# Display.net
KiCad netlist of a schematic drawn in Altium Designer
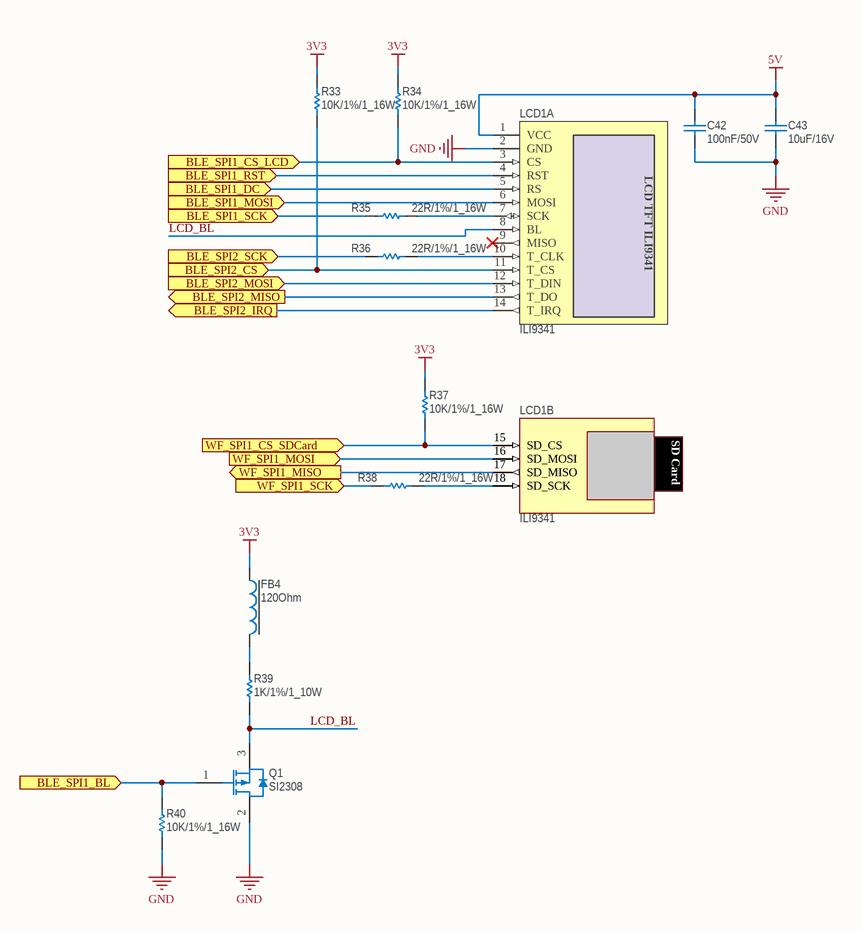
[diagram p0: Display.SchDoc]

(export (version "E")
  (design (tool "Eeschema 10.0.6"))
  (components
    (comp (ref "C42")
      (value "100nF/50V")
      (footprint "CAP_0603")
      (description "CAP, size 0603, 100nF, 50V")
      (fields (field (name "SUPPLY PART NUMBER") "Tụ Gốm 0603 100nF (0.1uF) 50V"))
      (libsource (lib "BluetoothTracking") (part "Ceramic_Cap_100nF_50V_0603"))
    )
    (comp (ref "C43")
      (value "10uF/16V")
      (footprint "CAP_0603")
      (description "CAP, size 0603, 10uF, 16V")
      (fields (field (name "SUPPLY PART NUMBER") "Tụ Gốm 0603 10uF 16V"))
      (libsource (lib "BluetoothTracking") (part "Ceramic_Cap_10uF_16V_0603"))
    )
    (comp (ref "FB4")
      (value "120Ohm")
      (footprint "Ferrite_Bead_0805")
      (description "Ferrite Bead, size 0805, 120Ohm, 2A")
      (fields (field (name "SUPPLY PART NUMBER") "CBW201209U121T Ferrite Beads 2A 120 Ohm 0805"))
      (libsource (lib "BluetoothTracking") (part "Ferrite_Bead_120Ohm_2A_0805"))
    )
    (comp (ref "LCD1")
      (value "ILI9341")
      (footprint "LCD_TFT_ILI9341_3.2")
      (fields (field (name "SUPPLY PART NUMBER") "LCD 3.2inch 320x240 TFT ILI9341 Cảm Ứng Điện Trở SPI"))
      (libsource (lib "BluetoothTracking") (part "LCD TFT"))
    )
    (comp (ref "Q1")
      (value "SI2308")
      (footprint "SOT-23")
      (description "SI2308 SOT23 MOSFET N-CH 2A 60V")
      (libsource (lib "BluetoothTracking") (part "SI2308"))
    )
    (comp (ref "R33")
      (value "10K/1%/1_16W")
      (footprint "RESISTOR_0402")
      (description "Resistor 0402 10KOhm 1% 1_16W")
      (fields (field (name "SUPPLY PART NUMBER") "Điện Trở 10 KOhm 0402 1%"))
      (libsource (lib "BluetoothTracking") (part "Res_10K_0402_1%"))
    )
    (comp (ref "R34")
      (value "10K/1%/1_16W")
      (footprint "RESISTOR_0402")
      (description "Resistor 0402 10KOhm 1% 1_16W")
      (fields (field (name "SUPPLY PART NUMBER") "Điện Trở 10 KOhm 0402 1%"))
      (libsource (lib "BluetoothTracking") (part "Res_10K_0402_1%"))
    )
    (comp (ref "R35")
      (value "22R/1%/1_16W")
      (footprint "RESISTOR_0402")
      (description "Resistor 0402 22 Ohm 1% 1_16W")
      (libsource (lib "BluetoothTracking") (part "Res_22R_0402_1%"))
    )
    (comp (ref "R36")
      (value "22R/1%/1_16W")
      (footprint "RESISTOR_0402")
      (description "Resistor 0402 22 Ohm 1% 1_16W")
      (libsource (lib "BluetoothTracking") (part "Res_22R_0402_1%"))
    )
    (comp (ref "R37")
      (value "10K/1%/1_16W")
      (footprint "RESISTOR_0402")
      (description "Resistor 0402 10KOhm 1% 1_16W")
      (fields (field (name "SUPPLY PART NUMBER") "Điện Trở 10 KOhm 0402 1%"))
      (libsource (lib "BluetoothTracking") (part "Res_10K_0402_1%"))
    )
    (comp (ref "R38")
      (value "22R/1%/1_16W")
      (footprint "RESISTOR_0402")
      (description "Resistor 0402 22 Ohm 1% 1_16W")
      (libsource (lib "BluetoothTracking") (part "Res_22R_0402_1%"))
    )
    (comp (ref "R39")
      (value "1K/1%/1_10W")
      (footprint "Resistor_0603")
      (description "Resistor 0603 1KOhm 1% 1_10W")
      (fields (field (name "SUPPLY PART NUMBER") "Điện Trở 1 KOhm 0603 1%"))
      (libsource (lib "BluetoothTracking") (part "Res_1K_0603_1%"))
    )
    (comp (ref "R40")
      (value "10K/1%/1_16W")
      (footprint "RESISTOR_0402")
      (description "Resistor 0402 10KOhm 1% 1_16W")
      (fields (field (name "SUPPLY PART NUMBER") "Điện Trở 10 KOhm 0402 1%"))
      (libsource (lib "BluetoothTracking") (part "Res_10K_0402_1%"))
    )
  )
  (nets
    (net (code "1") (name "/BLE_SPI1_BL") (class "Default")
      (node (ref "Q1") (pin "1") (pinfunction "GATE_1") (pintype "passive"))
      (node (ref "R40") (pin "2") (pinfunction "2_2") (pintype "passive"))
    )
    (net (code "2") (name "/BLE_SPI1_CS_LCD") (class "Default")
      (node (ref "LCD1") (pin "3") (pinfunction "CS_3") (pintype "input"))
      (node (ref "R34") (pin "1") (pinfunction "1_1") (pintype "passive"))
    )
    (net (code "3") (name "/BLE_SPI1_DC") (class "Default")
      (node (ref "LCD1") (pin "5") (pinfunction "RS_5") (pintype "input"))
    )
    (net (code "4") (name "/BLE_SPI1_MOSI") (class "Default")
      (node (ref "LCD1") (pin "6") (pinfunction "MOSI_6") (pintype "input"))
    )
    (net (code "5") (name "/BLE_SPI1_RST") (class "Default")
      (node (ref "LCD1") (pin "4") (pinfunction "RST_4") (pintype "input"))
    )
    (net (code "6") (name "/BLE_SPI1_SCK") (class "Default")
      (node (ref "R35") (pin "1") (pinfunction "1_1") (pintype "passive"))
    )
    (net (code "7") (name "/BLE_SPI2_CS") (class "Default")
      (node (ref "LCD1") (pin "11") (pinfunction "T_CS_11") (pintype "input"))
      (node (ref "R33") (pin "1") (pinfunction "1_1") (pintype "passive"))
    )
    (net (code "8") (name "/BLE_SPI2_IRQ") (class "Default")
      (node (ref "LCD1") (pin "14") (pinfunction "T_IRQ_14") (pintype "output"))
    )
    (net (code "9") (name "/BLE_SPI2_MISO") (class "Default")
      (node (ref "LCD1") (pin "13") (pinfunction "T_DO_13") (pintype "output"))
    )
    (net (code "10") (name "/BLE_SPI2_MOSI") (class "Default")
      (node (ref "LCD1") (pin "12") (pinfunction "T_DIN_12") (pintype "input"))
    )
    (net (code "11") (name "/BLE_SPI2_SCK") (class "Default")
      (node (ref "R36") (pin "1") (pinfunction "1_1") (pintype "passive"))
    )
    (net (code "12") (name "/LCD_BL") (class "Default")
      (node (ref "LCD1") (pin "8") (pinfunction "BL_8") (pintype "input"))
      (node (ref "Q1") (pin "3") (pinfunction "DRAIN_3") (pintype "passive"))
      (node (ref "R39") (pin "1") (pinfunction "1_1") (pintype "passive"))
    )
    (net (code "13") (name "/WF_SPI1_CS_SDCard") (class "Default")
      (node (ref "LCD1") (pin "15") (pinfunction "SD_CS_15") (pintype "input"))
      (node (ref "R37") (pin "1") (pinfunction "1_1") (pintype "passive"))
    )
    (net (code "14") (name "/WF_SPI1_MISO") (class "Default")
      (node (ref "LCD1") (pin "17") (pinfunction "SD_MISO_17") (pintype "output"))
    )
    (net (code "15") (name "/WF_SPI1_MOSI") (class "Default")
      (node (ref "LCD1") (pin "16") (pinfunction "SD_MOSI_16") (pintype "input"))
    )
    (net (code "16") (name "/WF_SPI1_SCK") (class "Default")
      (node (ref "R38") (pin "1") (pinfunction "1_1") (pintype "passive"))
    )
    (net (code "17") (name "3V3") (class "Default")
      (node (ref "FB4") (pin "1") (pinfunction "1_1") (pintype "passive"))
      (node (ref "R33") (pin "2") (pinfunction "2_2") (pintype "passive"))
      (node (ref "R34") (pin "2") (pinfunction "2_2") (pintype "passive"))
      (node (ref "R37") (pin "2") (pinfunction "2_2") (pintype "passive"))
    )
    (net (code "18") (name "5V") (class "Default")
      (node (ref "C42") (pin "2") (pinfunction "2_2") (pintype "passive"))
      (node (ref "C43") (pin "2") (pinfunction "2_2") (pintype "passive"))
      (node (ref "LCD1") (pin "1") (pinfunction "VCC_1") (pintype "power_in"))
    )
    (net (code "19") (name "GND") (class "Default")
      (node (ref "C42") (pin "1") (pinfunction "1_1") (pintype "passive"))
      (node (ref "C43") (pin "1") (pinfunction "1_1") (pintype "passive"))
      (node (ref "LCD1") (pin "2") (pinfunction "GND_2") (pintype "power_in"))
      (node (ref "Q1") (pin "2") (pinfunction "SOURCE_2") (pintype "passive"))
      (node (ref "R40") (pin "1") (pinfunction "1_1") (pintype "passive"))
    )
    (net (code "20") (name "Net-(FB4-Pad2)") (class "Default")
      (node (ref "FB4") (pin "2") (pinfunction "2_2") (pintype "passive"))
      (node (ref "R39") (pin "2") (pinfunction "2_2") (pintype "passive"))
    )
    (net (code "21") (name "Net-(LCD1A-SCK)") (class "Default")
      (node (ref "LCD1") (pin "7") (pinfunction "SCK_7") (pintype "bidirectional"))
      (node (ref "R35") (pin "2") (pinfunction "2_2") (pintype "passive"))
    )
    (net (code "22") (name "Net-(LCD1A-T_CLK)") (class "Default")
      (node (ref "LCD1") (pin "10") (pinfunction "T_CLK_10") (pintype "input"))
      (node (ref "R36") (pin "2") (pinfunction "2_2") (pintype "passive"))
    )
    (net (code "23") (name "Net-(LCD1B-SD_SCK)") (class "Default")
      (node (ref "LCD1") (pin "18") (pinfunction "SD_SCK_18") (pintype "input"))
      (node (ref "R38") (pin "2") (pinfunction "2_2") (pintype "passive"))
    )
    (net (code "24") (name "unconnected-(LCD1A-MISO-Pad9)") (class "Default")
      (node (ref "LCD1") (pin "9") (pinfunction "MISO_9") (pintype "output+no_connect"))
    )
  )
)
